# Adafruit_BrainCraft_HAT.net
KiCad netlist of a schematic drawn in EAGLE
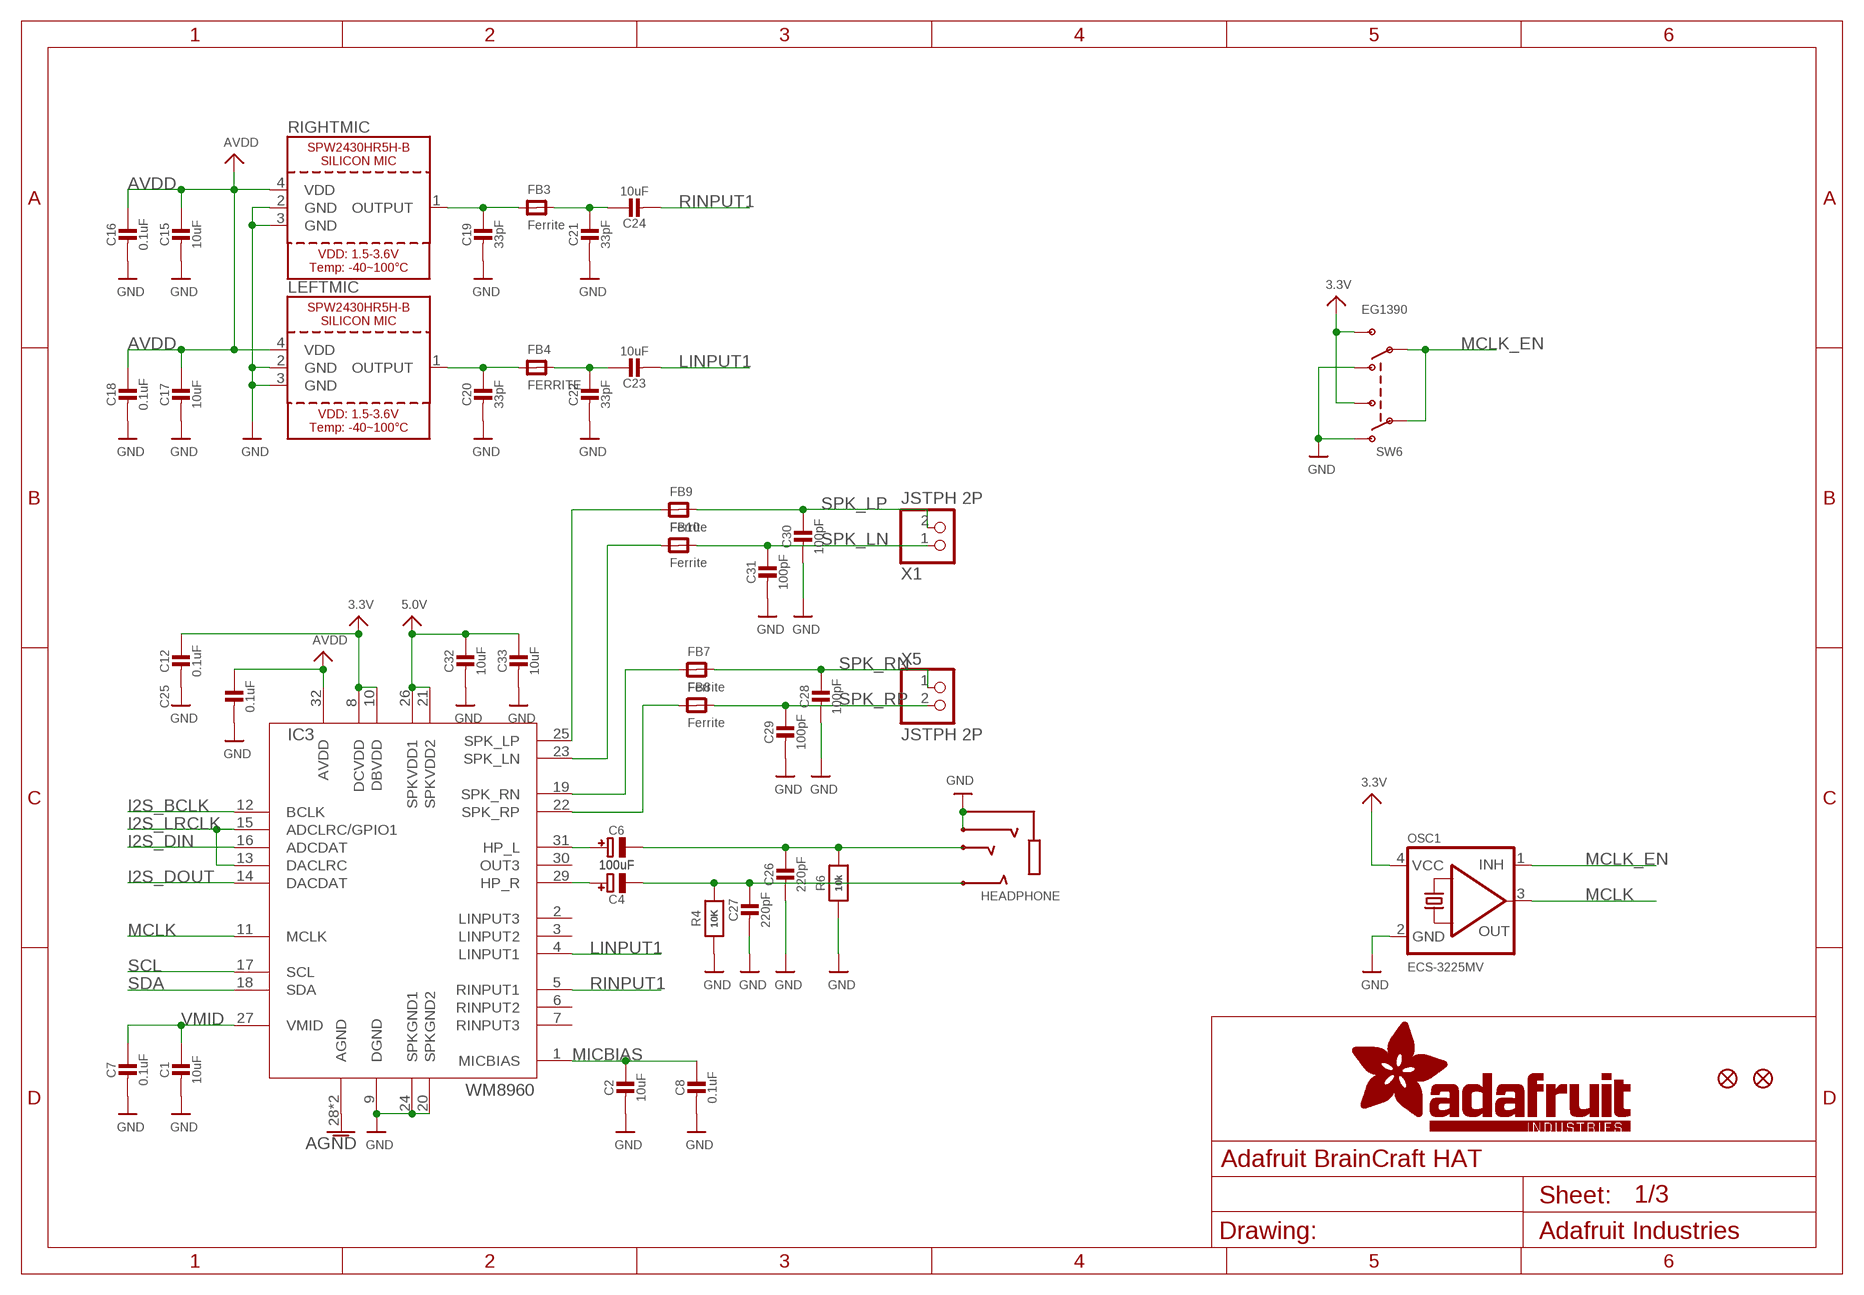
[diagram p0: schematic, sheet 1]
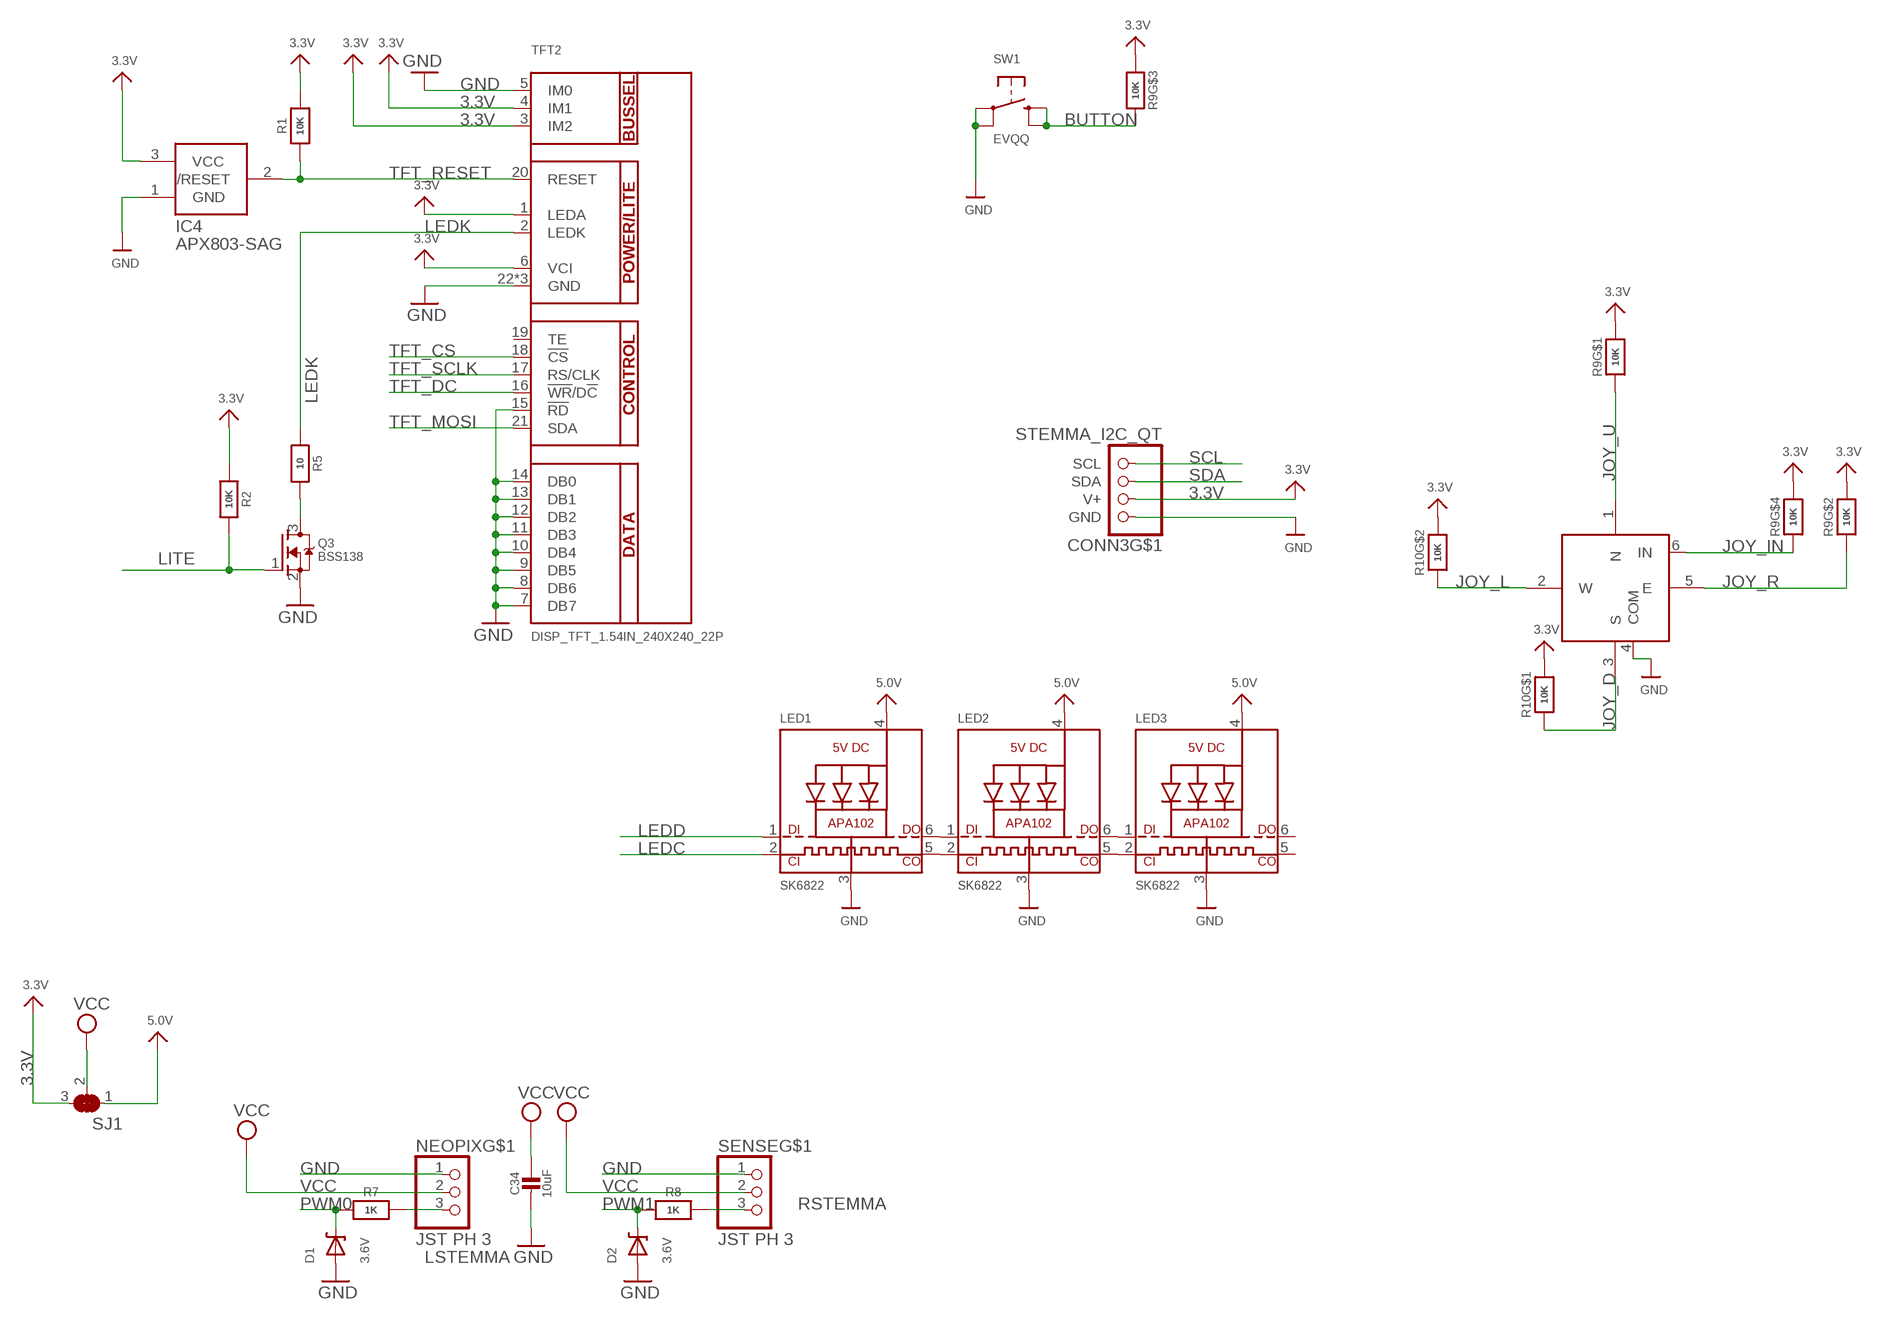
[diagram p1: schematic, sheet 2]
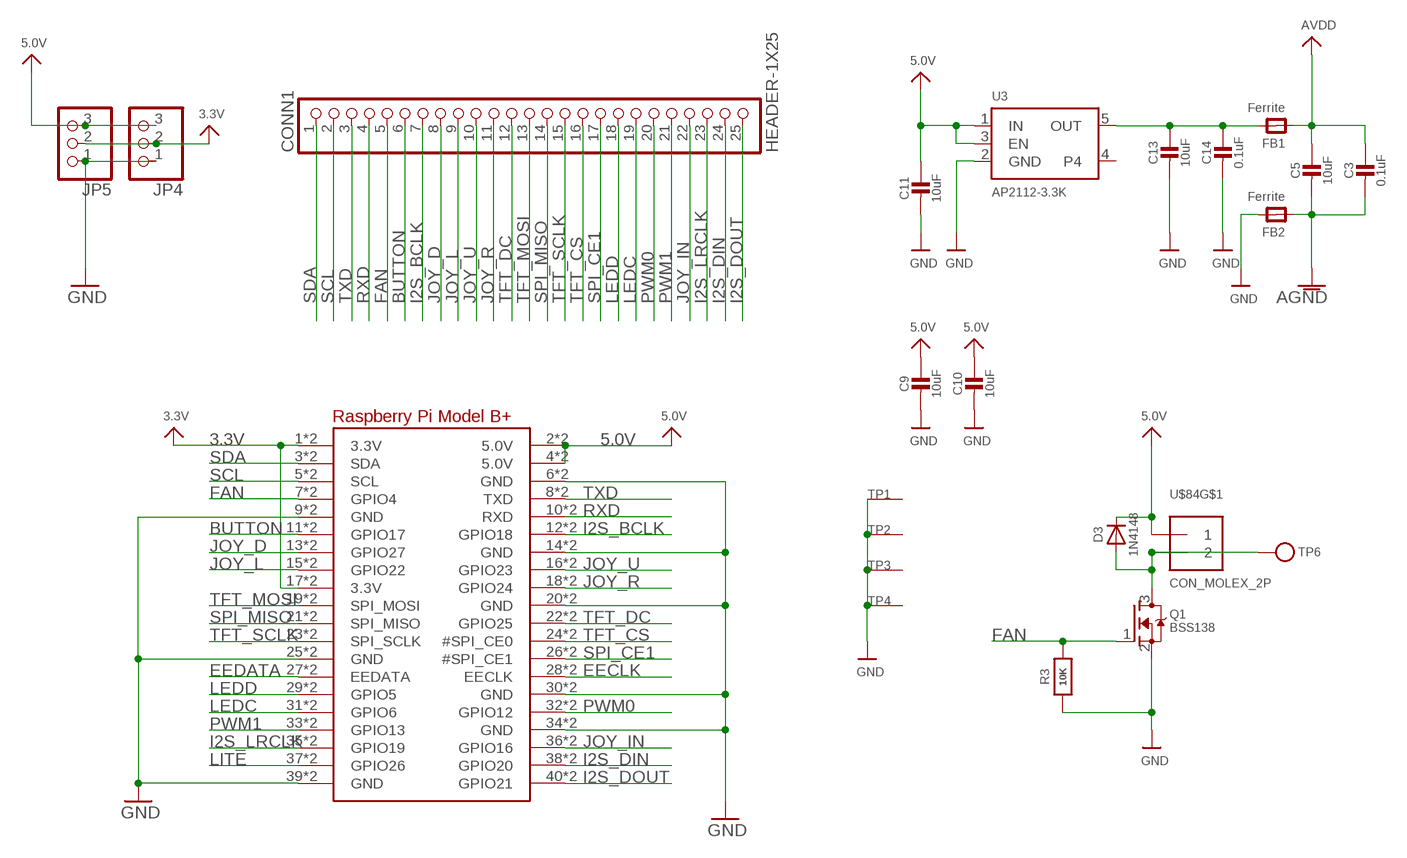
[diagram p2: schematic, sheet 3]

(export (version "E")
  (design (tool "Eeschema 10.0.6"))
  (components
    (comp (ref "C34")
      (value "10uF")
      (footprint "eagle-import:0805-NO")
      (libsource (lib "eagle-import") (part "CAP_CERAMIC0805-NOOUTLINE"))
    )
    (comp (ref "CONN3")
      (value "STEMMA_I2C_QT")
      (footprint "eagle-import:JST_SH4")
      (libsource (lib "eagle-import") (part "STEMMA_I2C_QT"))
    )
    (comp (ref "D1")
      (value "3.6V")
      (footprint "eagle-import:SOD-323")
      (libsource (lib "eagle-import") (part "DIODE-ZENERSOD323"))
    )
    (comp (ref "D2")
      (value "3.6V")
      (footprint "eagle-import:SOD-323")
      (libsource (lib "eagle-import") (part "DIODE-ZENERSOD323"))
    )
    (comp (ref "IC4")
      (value "APX803-SAG")
      (footprint "eagle-import:SOT23")
      (libsource (lib "eagle-import") (part "AXP083-SAG"))
    )
    (comp (ref "LED1")
      (value "SK6822")
      (footprint "eagle-import:APA102")
      (libsource (lib "eagle-import") (part "APA102"))
    )
    (comp (ref "LED2")
      (value "SK6822")
      (footprint "eagle-import:APA102")
      (libsource (lib "eagle-import") (part "APA102"))
    )
    (comp (ref "LED3")
      (value "SK6822")
      (footprint "eagle-import:APA102")
      (libsource (lib "eagle-import") (part "APA102"))
    )
    (comp (ref "NEOPIX")
      (value "JST PH 3")
      (footprint "eagle-import:JSTPH3")
      (libsource (lib "eagle-import") (part "CON_JST_PH_3PIN"))
    )
    (comp (ref "Q3")
      (value "BSS138")
      (footprint "eagle-import:SOT23-WIDE")
      (libsource (lib "eagle-import") (part "MOSFET-NWIDE"))
    )
    (comp (ref "R1")
      (value "10K")
      (footprint "eagle-import:0603-NO")
      (libsource (lib "eagle-import") (part "RESISTOR_0603_NOOUT"))
    )
    (comp (ref "R2")
      (value "10K")
      (footprint "eagle-import:0603-NO")
      (libsource (lib "eagle-import") (part "RESISTOR_0603_NOOUT"))
    )
    (comp (ref "R5")
      (value "10")
      (footprint "eagle-import:0603-NO")
      (libsource (lib "eagle-import") (part "RESISTOR_0603_NOOUT"))
    )
    (comp (ref "R7")
      (value "1K")
      (footprint "eagle-import:0603-NO")
      (libsource (lib "eagle-import") (part "RESISTOR_0603_NOOUT"))
    )
    (comp (ref "R8")
      (value "1K")
      (footprint "eagle-import:0603-NO")
      (libsource (lib "eagle-import") (part "RESISTOR_0603_NOOUT"))
    )
    (comp (ref "R9")
      (value "10K")
      (footprint "eagle-import:RESPACK_4X0603")
      (libsource (lib "eagle-import") (part "RESISTOR_4PACK"))
    )
    (comp (ref "R10")
      (value "10K")
      (footprint "eagle-import:RESPACK_4X0603")
      (libsource (lib "eagle-import") (part "RESISTOR_4PACK"))
    )
    (comp (ref "SENSE")
      (value "JST PH 3")
      (footprint "eagle-import:JSTPH3")
      (libsource (lib "eagle-import") (part "CON_JST_PH_3PIN"))
    )
    (comp (ref "SJ1")
      (value "SOLDERJUMPER_2WAY")
      (footprint "eagle-import:SOLDERJUMPER_2WAY_OPEN_NOPASTE")
      (libsource (lib "eagle-import") (part "SOLDERJUMPER_2WAY"))
    )
    (comp (ref "SW1")
      (value "EVQQ")
      (footprint "eagle-import:EVQ-Q2_SMALLER")
      (libsource (lib "eagle-import") (part "SWITCH_TACT_SMT_EVQQ2_SMALL"))
    )
    (comp (ref "SW5")
      (value "NAVSWITCHSKQUABAUE010")
      (footprint "eagle-import:SKQUBAE010")
      (libsource (lib "eagle-import") (part "NAVSWITCHSKQUABAUE010"))
    )
    (comp (ref "TFT2")
      (value "DISP_TFT_1.54IN_240X240_22P")
      (footprint "eagle-import:TFT_1.54IN_240X240_22PIN")
      (libsource (lib "eagle-import") (part "DISP_TFT_1.54IN_240X240_22P"))
    )
    (comp (ref "C3")
      (value "0.1uF")
      (footprint "eagle-import:0603-NO")
      (libsource (lib "eagle-import") (part "CAP_CERAMIC0603_NO"))
    )
    (comp (ref "C5")
      (value "10uF")
      (footprint "eagle-import:0805-NO")
      (libsource (lib "eagle-import") (part "CAP_CERAMIC0805-NOOUTLINE"))
    )
    (comp (ref "C9")
      (value "10uF")
      (footprint "eagle-import:0805-NO")
      (libsource (lib "eagle-import") (part "CAP_CERAMIC0805-NOOUTLINE"))
    )
    (comp (ref "C10")
      (value "10uF")
      (footprint "eagle-import:0805-NO")
      (libsource (lib "eagle-import") (part "CAP_CERAMIC0805-NOOUTLINE"))
    )
    (comp (ref "C11")
      (value "10uF")
      (footprint "eagle-import:0805-NO")
      (libsource (lib "eagle-import") (part "CAP_CERAMIC0805-NOOUTLINE"))
    )
    (comp (ref "C13")
      (value "10uF")
      (footprint "eagle-import:0805-NO")
      (libsource (lib "eagle-import") (part "CAP_CERAMIC0805-NOOUTLINE"))
    )
    (comp (ref "C14")
      (value "0.1uF")
      (footprint "eagle-import:0603-NO")
      (libsource (lib "eagle-import") (part "CAP_CERAMIC0603_NO"))
    )
    (comp (ref "CONN1")
      (value "HEADER-1X25")
      (footprint "eagle-import:1X25_ROUND_70MIL")
      (libsource (lib "eagle-import") (part "HEADER-1X25"))
    )
    (comp (ref "D3")
      (value "1N4148")
      (footprint "eagle-import:SOD-323")
      (libsource (lib "eagle-import") (part "DIODESOD-323"))
    )
    (comp (ref "FB1")
      (value "Ferrite")
      (footprint "eagle-import:0805")
      (libsource (lib "eagle-import") (part "FERRITE0805"))
    )
    (comp (ref "FB2")
      (value "Ferrite")
      (footprint "eagle-import:0805")
      (libsource (lib "eagle-import") (part "FERRITE0805"))
    )
    (comp (ref "JP4")
      (value "HEADER-1X376MIL")
      (footprint "eagle-import:1X03_ROUND_76")
      (libsource (lib "eagle-import") (part "HEADER-1X376MIL"))
    )
    (comp (ref "JP5")
      (value "HEADER-1X376MIL")
      (footprint "eagle-import:1X03_ROUND_76")
      (libsource (lib "eagle-import") (part "HEADER-1X376MIL"))
    )
    (comp (ref "Q1")
      (value "BSS138")
      (footprint "eagle-import:SOT23-WIDE")
      (libsource (lib "eagle-import") (part "MOSFET-NWIDE"))
    )
    (comp (ref "R3")
      (value "10K")
      (footprint "eagle-import:0603-NO")
      (libsource (lib "eagle-import") (part "RESISTOR_0603_NOOUT"))
    )
    (comp (ref "RPI1")
      (value "RASPBERRYPI_BPLUS_HAT_SMTTHM_SLOTS")
      (footprint "eagle-import:PI_HAT_SMTTHM_SLOTS")
      (libsource (lib "eagle-import") (part "RASPBERRYPI_BPLUS_HAT_SMTTHM_SLOTS"))
    )
    (comp (ref "TP1")
      (value "SEWTAP_SMTNUTM3")
      (footprint "eagle-import:SMT_NUT_3MM")
      (libsource (lib "eagle-import") (part "SEWTAP_SMTNUTM3"))
    )
    (comp (ref "TP2")
      (value "SEWTAP_SMTNUTM3")
      (footprint "eagle-import:SMT_NUT_3MM")
      (libsource (lib "eagle-import") (part "SEWTAP_SMTNUTM3"))
    )
    (comp (ref "TP3")
      (value "SEWTAP_SMTNUTM3")
      (footprint "eagle-import:SMT_NUT_3MM")
      (libsource (lib "eagle-import") (part "SEWTAP_SMTNUTM3"))
    )
    (comp (ref "TP4")
      (value "SEWTAP_SMTNUTM3")
      (footprint "eagle-import:SMT_NUT_3MM")
      (libsource (lib "eagle-import") (part "SEWTAP_SMTNUTM3"))
    )
    (comp (ref "TP6")
      (value "TESTPOINTROUND2MM")
      (footprint "eagle-import:TESTPOINT_ROUND_2MM")
      (libsource (lib "eagle-import") (part "TESTPOINTROUND2MM"))
    )
    (comp (ref "U$84")
      (value "CON_MOLEX_2P")
      (footprint "eagle-import:53398-0271")
      (libsource (lib "eagle-import") (part "CON_MOLEX_2P"))
    )
    (comp (ref "U3")
      (value "AP2112-3.3K")
      (footprint "eagle-import:SOT23-5")
      (libsource (lib "eagle-import") (part "VREG_SOT23-5"))
    )
    (comp (ref "C1")
      (value "10uF")
      (footprint "eagle-import:0805-NO")
      (libsource (lib "eagle-import") (part "CAP_CERAMIC0805-NOOUTLINE"))
    )
    (comp (ref "C2")
      (value "10uF")
      (footprint "eagle-import:0805-NO")
      (libsource (lib "eagle-import") (part "CAP_CERAMIC0805-NOOUTLINE"))
    )
    (comp (ref "C4")
      (value "100uF")
      (footprint "eagle-import:PANASONIC_C")
      (libsource (lib "eagle-import") (part "CAP_ELECTROLYTICPANASONIC_C"))
    )
    (comp (ref "C6")
      (value "100uF")
      (footprint "eagle-import:PANASONIC_C")
      (libsource (lib "eagle-import") (part "CAP_ELECTROLYTICPANASONIC_C"))
    )
    (comp (ref "C7")
      (value "0.1uF")
      (footprint "eagle-import:0603-NO")
      (libsource (lib "eagle-import") (part "CAP_CERAMIC0603_NO"))
    )
    (comp (ref "C8")
      (value "0.1uF")
      (footprint "eagle-import:0603-NO")
      (libsource (lib "eagle-import") (part "CAP_CERAMIC0603_NO"))
    )
    (comp (ref "C12")
      (value "0.1uF")
      (footprint "eagle-import:0603-NO")
      (libsource (lib "eagle-import") (part "CAP_CERAMIC0603_NO"))
    )
    (comp (ref "C15")
      (value "10uF")
      (footprint "eagle-import:0805-NO")
      (libsource (lib "eagle-import") (part "CAP_CERAMIC0805-NOOUTLINE"))
    )
    (comp (ref "C16")
      (value "0.1uF")
      (footprint "eagle-import:0603-NO")
      (libsource (lib "eagle-import") (part "CAP_CERAMIC0603_NO"))
    )
    (comp (ref "C17")
      (value "10uF")
      (footprint "eagle-import:0805-NO")
      (libsource (lib "eagle-import") (part "CAP_CERAMIC0805-NOOUTLINE"))
    )
    (comp (ref "C18")
      (value "0.1uF")
      (footprint "eagle-import:0603-NO")
      (libsource (lib "eagle-import") (part "CAP_CERAMIC0603_NO"))
    )
    (comp (ref "C19")
      (value "33pF")
      (footprint "eagle-import:0603-NO")
      (libsource (lib "eagle-import") (part "CAP_CERAMIC0603_NO"))
    )
    (comp (ref "C20")
      (value "33pF")
      (footprint "eagle-import:0603-NO")
      (libsource (lib "eagle-import") (part "CAP_CERAMIC0603_NO"))
    )
    (comp (ref "C21")
      (value "33pF")
      (footprint "eagle-import:0603-NO")
      (libsource (lib "eagle-import") (part "CAP_CERAMIC0603_NO"))
    )
    (comp (ref "C22")
      (value "33pF")
      (footprint "eagle-import:0603-NO")
      (libsource (lib "eagle-import") (part "CAP_CERAMIC0603_NO"))
    )
    (comp (ref "C23")
      (value "10uF")
      (footprint "eagle-import:0805-NO")
      (libsource (lib "eagle-import") (part "CAP_CERAMIC0805-NOOUTLINE"))
    )
    (comp (ref "C24")
      (value "10uF")
      (footprint "eagle-import:0805-NO")
      (libsource (lib "eagle-import") (part "CAP_CERAMIC0805-NOOUTLINE"))
    )
    (comp (ref "C25")
      (value "0.1uF")
      (footprint "eagle-import:0603-NO")
      (libsource (lib "eagle-import") (part "CAP_CERAMIC0603_NO"))
    )
    (comp (ref "C26")
      (value "220pF")
      (footprint "eagle-import:0603-NO")
      (libsource (lib "eagle-import") (part "CAP_CERAMIC0603_NO"))
    )
    (comp (ref "C27")
      (value "220pF")
      (footprint "eagle-import:0603-NO")
      (libsource (lib "eagle-import") (part "CAP_CERAMIC0603_NO"))
    )
    (comp (ref "C28")
      (value "100pF")
      (footprint "eagle-import:0603-NO")
      (libsource (lib "eagle-import") (part "CAP_CERAMIC0603_NO"))
    )
    (comp (ref "C29")
      (value "100pF")
      (footprint "eagle-import:0603-NO")
      (libsource (lib "eagle-import") (part "CAP_CERAMIC0603_NO"))
    )
    (comp (ref "C30")
      (value "100pF")
      (footprint "eagle-import:0603-NO")
      (libsource (lib "eagle-import") (part "CAP_CERAMIC0603_NO"))
    )
    (comp (ref "C31")
      (value "100pF")
      (footprint "eagle-import:0603-NO")
      (libsource (lib "eagle-import") (part "CAP_CERAMIC0603_NO"))
    )
    (comp (ref "C32")
      (value "10uF")
      (footprint "eagle-import:0805-NO")
      (libsource (lib "eagle-import") (part "CAP_CERAMIC0805-NOOUTLINE"))
    )
    (comp (ref "C33")
      (value "10uF")
      (footprint "eagle-import:0805-NO")
      (libsource (lib "eagle-import") (part "CAP_CERAMIC0805-NOOUTLINE"))
    )
    (comp (ref "FB3")
      (value "Ferrite")
      (footprint "eagle-import:0805-NO")
      (libsource (lib "eagle-import") (part "FERRITE-0805NO"))
    )
    (comp (ref "FB4")
      (value "FERRITE")
      (footprint "eagle-import:0805-NO")
      (libsource (lib "eagle-import") (part "FERRITE-0805NO"))
    )
    (comp (ref "FB7")
      (value "Ferrite")
      (footprint "eagle-import:0805-NO")
      (libsource (lib "eagle-import") (part "FERRITE-0805NO"))
    )
    (comp (ref "FB8")
      (value "Ferrite")
      (footprint "eagle-import:0805-NO")
      (libsource (lib "eagle-import") (part "FERRITE-0805NO"))
    )
    (comp (ref "FB9")
      (value "Ferrite")
      (footprint "eagle-import:0805-NO")
      (libsource (lib "eagle-import") (part "FERRITE-0805NO"))
    )
    (comp (ref "FB10")
      (value "Ferrite")
      (footprint "eagle-import:0805-NO")
      (libsource (lib "eagle-import") (part "FERRITE-0805NO"))
    )
    (comp (ref "FID1")
      (value "FIDUCIAL_1MM")
      (footprint "eagle-import:FIDUCIAL_1MM")
      (libsource (lib "eagle-import") (part "FIDUCIAL_1MM"))
    )
    (comp (ref "FID2")
      (value "FIDUCIAL_1MM")
      (footprint "eagle-import:FIDUCIAL_1MM")
      (libsource (lib "eagle-import") (part "FIDUCIAL_1MM"))
    )
    (comp (ref "HEADPHONE")
      (value "AUDIO_3.5MMJACK_4POL")
      (footprint "eagle-import:4UCONN_18510")
      (libsource (lib "eagle-import") (part "AUDIO_3.5MMJACK_4POL"))
    )
    (comp (ref "IC3")
      (value "WM8960")
      (footprint "eagle-import:QFN32_5MM")
      (libsource (lib "eagle-import") (part "WM8960"))
    )
    (comp (ref "LEFTMIC")
      (value "SPW2430HR5H-B")
      (footprint "eagle-import:SPW2430HR5H-B")
      (libsource (lib "eagle-import") (part "SPW2430HR5H-B"))
    )
    (comp (ref "OSC1")
      (value "ECS-3225MV")
      (footprint "eagle-import:OSC_3.2X2.5MM")
      (libsource (lib "eagle-import") (part "OSCILLATOR3.2X2.5"))
    )
    (comp (ref "R4")
      (value "10K")
      (footprint "eagle-import:0603-NO")
      (libsource (lib "eagle-import") (part "RESISTOR_0603_NOOUT"))
    )
    (comp (ref "R6")
      (value "10k")
      (footprint "eagle-import:0603-NO")
      (libsource (lib "eagle-import") (part "RESISTOR_0603_NOOUT"))
    )
    (comp (ref "RIGHTMIC")
      (value "SPW2430HR5H-B")
      (footprint "eagle-import:SPW2430HR5H-B")
      (libsource (lib "eagle-import") (part "SPW2430HR5H-B"))
    )
    (comp (ref "SW6")
      (value "EG1390")
      (footprint "eagle-import:EG1390")
      (libsource (lib "eagle-import") (part "SWITCH_DPDTEG1390"))
    )
    (comp (ref "X1")
      (value "JSTPH 2P")
      (footprint "eagle-import:JSTPH2")
      (libsource (lib "eagle-import") (part "CON_JST_PH_2PIN"))
    )
    (comp (ref "X5")
      (value "JSTPH 2P")
      (footprint "eagle-import:JSTPH2")
      (libsource (lib "eagle-import") (part "CON_JST_PH_2PIN"))
    )
  )
  (nets
    (net (code "1") (name "3.3V") (class "Default")
      (node (ref "C12") (pin "1") (pinfunction "1_1") (pintype "passive"))
      (node (ref "CONN3") (pin "2") (pinfunction "V+_2") (pintype "passive"))
      (node (ref "IC3") (pin "10") (pinfunction "DBVDD_10") (pintype "power_in"))
      (node (ref "IC3") (pin "8") (pinfunction "DCVDD_8") (pintype "power_in"))
      (node (ref "IC4") (pin "3") (pinfunction "VCC_3") (pintype "power_in"))
      (node (ref "JP4") (pin "2") (pinfunction "2_2") (pintype "passive"))
      (node (ref "JP5") (pin "2") (pinfunction "2_2") (pintype "passive"))
      (node (ref "OSC1") (pin "4") (pinfunction "VCC_4") (pintype "power_in"))
      (node (ref "R1") (pin "2") (pinfunction "2_2") (pintype "passive"))
      (node (ref "R10") (pin "7") (pinfunction "2_7") (pintype "passive"))
      (node (ref "R10") (pin "8") (pinfunction "2_8") (pintype "passive"))
      (node (ref "R2") (pin "2") (pinfunction "2_2") (pintype "passive"))
      (node (ref "R9") (pin "5") (pinfunction "2_5") (pintype "passive"))
      (node (ref "R9") (pin "6") (pinfunction "2_6") (pintype "passive"))
      (node (ref "R9") (pin "7") (pinfunction "2_7") (pintype "passive"))
      (node (ref "R9") (pin "8") (pinfunction "2_8") (pintype "passive"))
      (node (ref "RPI1") (pin "1") (pinfunction "3.3V_1") (pintype "power_in"))
      (node (ref "RPI1") (pin "17") (pinfunction "3.3V_17") (pintype "power_in"))
      (node (ref "RPI1") (pin "S1") (pinfunction "3.3V_S1") (pintype "power_in"))
      (node (ref "RPI1") (pin "S17") (pinfunction "3.3V_S17") (pintype "power_in"))
      (node (ref "SJ1") (pin "3") (pinfunction "3_3") (pintype "passive"))
      (node (ref "SW6") (pin "S1") (pinfunction "S1_S1") (pintype "passive"))
      (node (ref "SW6") (pin "S2") (pinfunction "S2_S2") (pintype "passive"))
      (node (ref "TFT2") (pin "1") (pinfunction "LEDA_1") (pintype "input"))
      (node (ref "TFT2") (pin "3") (pinfunction "IM2_3") (pintype "input"))
      (node (ref "TFT2") (pin "4") (pinfunction "IM1_4") (pintype "input"))
      (node (ref "TFT2") (pin "6") (pinfunction "VCI_6") (pintype "power_in"))
    )
    (net (code "2") (name "5.0V") (class "Default")
      (node (ref "C10") (pin "1") (pinfunction "1_1") (pintype "passive"))
      (node (ref "C11") (pin "1") (pinfunction "1_1") (pintype "passive"))
      (node (ref "C32") (pin "1") (pinfunction "1_1") (pintype "passive"))
      (node (ref "C33") (pin "1") (pinfunction "1_1") (pintype "passive"))
      (node (ref "C9") (pin "1") (pinfunction "1_1") (pintype "passive"))
      (node (ref "D3") (pin "C") (pinfunction "C_C") (pintype "passive"))
      (node (ref "IC3") (pin "21") (pinfunction "SPKVDD2_21") (pintype "power_in"))
      (node (ref "IC3") (pin "26") (pinfunction "SPKVDD1_26") (pintype "power_in"))
      (node (ref "JP4") (pin "3") (pinfunction "3_3") (pintype "passive"))
      (node (ref "JP5") (pin "3") (pinfunction "3_3") (pintype "passive"))
      (node (ref "LED1") (pin "4") (pinfunction "VDD_4") (pintype "power_in"))
      (node (ref "LED2") (pin "4") (pinfunction "VDD_4") (pintype "power_in"))
      (node (ref "LED3") (pin "4") (pinfunction "VDD_4") (pintype "power_in"))
      (node (ref "RPI1") (pin "2") (pinfunction "5.0V_2") (pintype "power_in"))
      (node (ref "RPI1") (pin "4") (pinfunction "5.0V_4") (pintype "power_in"))
      (node (ref "RPI1") (pin "S2") (pinfunction "5.0V_S2") (pintype "power_in"))
      (node (ref "RPI1") (pin "S4") (pinfunction "5.0V_S4") (pintype "power_in"))
      (node (ref "SJ1") (pin "1") (pinfunction "1_1") (pintype "passive"))
      (node (ref "U$84") (pin "1") (pinfunction "1_1") (pintype "passive"))
      (node (ref "U3") (pin "1") (pinfunction "IN_1") (pintype "power_in"))
      (node (ref "U3") (pin "3") (pinfunction "EN_3") (pintype "input"))
    )
    (net (code "3") (name "AGND") (class "Default")
      (node (ref "C3") (pin "2") (pinfunction "2_2") (pintype "passive"))
      (node (ref "C5") (pin "2") (pinfunction "2_2") (pintype "passive"))
      (node (ref "FB2") (pin "1") (pinfunction "P$1_1") (pintype "passive"))
      (node (ref "IC3") (pin "28") (pinfunction "AGND_28") (pintype "power_in"))
      (node (ref "IC3") (pin "33") (pinfunction "AGND_33") (pintype "power_in"))
    )
    (net (code "4") (name "AVDD") (class "Default")
      (node (ref "C15") (pin "1") (pinfunction "1_1") (pintype "passive"))
      (node (ref "C16") (pin "1") (pinfunction "1_1") (pintype "passive"))
      (node (ref "C17") (pin "1") (pinfunction "1_1") (pintype "passive"))
      (node (ref "C18") (pin "1") (pinfunction "1_1") (pintype "passive"))
      (node (ref "C25") (pin "1") (pinfunction "1_1") (pintype "passive"))
      (node (ref "C3") (pin "1") (pinfunction "1_1") (pintype "passive"))
      (node (ref "C5") (pin "1") (pinfunction "1_1") (pintype "passive"))
      (node (ref "FB1") (pin "1") (pinfunction "P$1_1") (pintype "passive"))
      (node (ref "IC3") (pin "32") (pinfunction "AVDD_32") (pintype "power_in"))
      (node (ref "LEFTMIC") (pin "4") (pinfunction "VDD_4") (pintype "power_in"))
      (node (ref "RIGHTMIC") (pin "4") (pinfunction "VDD_4") (pintype "power_in"))
    )
    (net (code "5") (name "BUTTON") (class "Default")
      (node (ref "CONN1") (pin "6") (pinfunction "6_6") (pintype "passive"))
      (node (ref "R9") (pin "3") (pinfunction "1_3") (pintype "passive"))
      (node (ref "RPI1") (pin "11") (pinfunction "GPIO17_11") (pintype "bidirectional"))
      (node (ref "RPI1") (pin "S11") (pinfunction "GPIO17_S11") (pintype "bidirectional"))
      (node (ref "SW1") (pin "B") (pinfunction "S_B") (pintype "passive"))
      (node (ref "SW1") (pin "B'") (pinfunction "S1_B'") (pintype "passive"))
    )
    (net (code "6") (name "EECLK") (class "Default")
      (node (ref "RPI1") (pin "28") (pinfunction "EECLK_28") (pintype "bidirectional"))
      (node (ref "RPI1") (pin "S28") (pinfunction "EECLK_S28") (pintype "bidirectional"))
    )
    (net (code "7") (name "EEDATA") (class "Default")
      (node (ref "RPI1") (pin "27") (pinfunction "EEDATA_27") (pintype "bidirectional"))
      (node (ref "RPI1") (pin "S27") (pinfunction "EEDATA_S27") (pintype "bidirectional"))
    )
    (net (code "8") (name "FAN") (class "Default")
      (node (ref "CONN1") (pin "5") (pinfunction "5_5") (pintype "passive"))
      (node (ref "Q1") (pin "1") (pinfunction "G_1") (pintype "bidirectional"))
      (node (ref "R3") (pin "1") (pinfunction "1_1") (pintype "passive"))
      (node (ref "RPI1") (pin "7") (pinfunction "GPIO4_7") (pintype "bidirectional"))
      (node (ref "RPI1") (pin "S7") (pinfunction "GPIO4_S7") (pintype "bidirectional"))
    )
    (net (code "9") (name "GND") (class "Default")
      (node (ref "C1") (pin "2") (pinfunction "2_2") (pintype "passive"))
      (node (ref "C10") (pin "2") (pinfunction "2_2") (pintype "passive"))
      (node (ref "C11") (pin "2") (pinfunction "2_2") (pintype "passive"))
      (node (ref "C12") (pin "2") (pinfunction "2_2") (pintype "passive"))
      (node (ref "C13") (pin "2") (pinfunction "2_2") (pintype "passive"))
      (node (ref "C14") (pin "2") (pinfunction "2_2") (pintype "passive"))
      (node (ref "C15") (pin "2") (pinfunction "2_2") (pintype "passive"))
      (node (ref "C16") (pin "2") (pinfunction "2_2") (pintype "passive"))
      (node (ref "C17") (pin "2") (pinfunction "2_2") (pintype "passive"))
      (node (ref "C18") (pin "2") (pinfunction "2_2") (pintype "passive"))
      (node (ref "C19") (pin "2") (pinfunction "2_2") (pintype "passive"))
      (node (ref "C2") (pin "2") (pinfunction "2_2") (pintype "passive"))
      (node (ref "C20") (pin "2") (pinfunction "2_2") (pintype "passive"))
      (node (ref "C21") (pin "2") (pinfunction "2_2") (pintype "passive"))
      (node (ref "C22") (pin "2") (pinfunction "2_2") (pintype "passive"))
      (node (ref "C25") (pin "2") (pinfunction "2_2") (pintype "passive"))
      (node (ref "C26") (pin "2") (pinfunction "2_2") (pintype "passive"))
      (node (ref "C27") (pin "2") (pinfunction "2_2") (pintype "passive"))
      (node (ref "C28") (pin "2") (pinfunction "2_2") (pintype "passive"))
      (node (ref "C29") (pin "2") (pinfunction "2_2") (pintype "passive"))
      (node (ref "C30") (pin "2") (pinfunction "2_2") (pintype "passive"))
      (node (ref "C31") (pin "2") (pinfunction "2_2") (pintype "passive"))
      (node (ref "C32") (pin "2") (pinfunction "2_2") (pintype "passive"))
      (node (ref "C33") (pin "2") (pinfunction "2_2") (pintype "passive"))
      (node (ref "C34") (pin "2") (pinfunction "2_2") (pintype "passive"))
      (node (ref "C7") (pin "2") (pinfunction "2_2") (pintype "passive"))
      (node (ref "C8") (pin "2") (pinfunction "2_2") (pintype "passive"))
      (node (ref "C9") (pin "2") (pinfunction "2_2") (pintype "passive"))
      (node (ref "CONN3") (pin "1") (pinfunction "GND_1") (pintype "passive"))
      (node (ref "D1") (pin "A") (pinfunction "A_A") (pintype "passive"))
      (node (ref "D2") (pin "A") (pinfunction "A_A") (pintype "passive"))
      (node (ref "FB2") (pin "2") (pinfunction "P$2_2") (pintype "passive"))
      (node (ref "HEADPHONE") (pin "1-GND") (pinfunction "TIP_1-GND") (pintype "passive"))
      (node (ref "HEADPHONE") (pin "4-INNER_SLEEVE") (pinfunction "RING1_4-INNER_SLEEVE") (pintype "passive"))
      (node (ref "IC3") (pin "20") (pinfunction "SPKGND2_20") (pintype "power_in"))
      (node (ref "IC3") (pin "24") (pinfunction "SPKGND1_24") (pintype "power_in"))
      (node (ref "IC3") (pin "9") (pinfunction "DGND_9") (pintype "power_in"))
      (node (ref "IC4") (pin "1") (pinfunction "GND_1") (pintype "power_in"))
      (node (ref "JP4") (pin "1") (pinfunction "1_1") (pintype "passive"))
      (node (ref "JP5") (pin "1") (pinfunction "1_1") (pintype "passive"))
      (node (ref "LED1") (pin "3") (pinfunction "GND_3") (pintype "power_in"))
      (node (ref "LED2") (pin "3") (pinfunction "GND_3") (pintype "power_in"))
      (node (ref "LED3") (pin "3") (pinfunction "GND_3") (pintype "power_in"))
      (node (ref "LEFTMIC") (pin "2") (pinfunction "GND_2") (pintype "power_in"))
      (node (ref "LEFTMIC") (pin "3") (pinfunction "GND_3") (pintype "power_in"))
      (node (ref "NEOPIX") (pin "1") (pinfunction "1_1") (pintype "passive"))
      (node (ref "OSC1") (pin "2") (pinfunction "GND_2") (pintype "power_in"))
      (node (ref "Q1") (pin "2") (pinfunction "S_2") (pintype "bidirectional"))
      (node (ref "Q3") (pin "2") (pinfunction "S_2") (pintype "bidirectional"))
      (node (ref "R3") (pin "2") (pinfunction "2_2") (pintype "passive"))
      (node (ref "R4") (pin "1") (pinfunction "1_1") (pintype "passive"))
      (node (ref "R6") (pin "1") (pinfunction "1_1") (pintype "passive"))
      (node (ref "RIGHTMIC") (pin "2") (pinfunction "GND_2") (pintype "power_in"))
      (node (ref "RIGHTMIC") (pin "3") (pinfunction "GND_3") (pintype "power_in"))
      (node (ref "RPI1") (pin "14") (pinfunction "GND_14") (pintype "power_in"))
      (node (ref "RPI1") (pin "20") (pinfunction "GND_20") (pintype "power_in"))
      (node (ref "RPI1") (pin "25") (pinfunction "GND_25") (pintype "power_in"))
      (node (ref "RPI1") (pin "30") (pinfunction "GND_30") (pintype "power_in"))
      (node (ref "RPI1") (pin "34") (pinfunction "GND_34") (pintype "power_in"))
      (node (ref "RPI1") (pin "39") (pinfunction "GND_39") (pintype "power_in"))
      (node (ref "RPI1") (pin "6") (pinfunction "GND_6") (pintype "power_in"))
      (node (ref "RPI1") (pin "9") (pinfunction "GND_9") (pintype "power_in"))
      (node (ref "RPI1") (pin "S14") (pinfunction "GND_S14") (pintype "power_in"))
      (node (ref "RPI1") (pin "S20") (pinfunction "GND_S20") (pintype "power_in"))
      (node (ref "RPI1") (pin "S25") (pinfunction "GND_S25") (pintype "power_in"))
      (node (ref "RPI1") (pin "S30") (pinfunction "GND_S30") (pintype "power_in"))
      (node (ref "RPI1") (pin "S34") (pinfunction "GND_S34") (pintype "power_in"))
      (node (ref "RPI1") (pin "S39") (pinfunction "GND_S39") (pintype "power_in"))
      (node (ref "RPI1") (pin "S6") (pinfunction "GND_S6") (pintype "power_in"))
      (node (ref "RPI1") (pin "S9") (pinfunction "GND_S9") (pintype "power_in"))
      (node (ref "SENSE") (pin "1") (pinfunction "1_1") (pintype "passive"))
      (node (ref "SW1") (pin "A") (pinfunction "P_A") (pintype "passive"))
      (node (ref "SW1") (pin "A'") (pinfunction "P1_A'") (pintype "passive"))
      (node (ref "SW5") (pin "4") (pinfunction "COM_4") (pintype "bidirectional"))
      (node (ref "SW6") (pin "O1") (pinfunction "O1_O1") (pintype "passive"))
      (node (ref "SW6") (pin "O2") (pinfunction "O2_O2") (pintype "passive"))
      (node (ref "TFT2") (pin "10") (pinfunction "DB4_10") (pintype "bidirectional"))
      (node (ref "TFT2") (pin "11") (pinfunction "DB3_11") (pintype "bidirectional"))
      (node (ref "TFT2") (pin "12") (pinfunction "DB2_12") (pintype "bidirectional"))
      (node (ref "TFT2") (pin "13") (pinfunction "DB1_13") (pintype "bidirectional"))
      (node (ref "TFT2") (pin "14") (pinfunction "DB0_14") (pintype "bidirectional"))
      (node (ref "TFT2") (pin "15") (pinfunction "~{RD}_15") (pintype "input"))
      (node (ref "TFT2") (pin "22") (pinfunction "GND_22") (pintype "power_in"))
      (node (ref "TFT2") (pin "5") (pinfunction "IM0_5") (pintype "input"))
      (node (ref "TFT2") (pin "7") (pinfunction "DB7_7") (pintype "bidirectional"))
      (node (ref "TFT2") (pin "8") (pinfunction "DB6_8") (pintype "bidirectional"))
      (node (ref "TFT2") (pin "9") (pinfunction "DB5_9") (pintype "bidirectional"))
      (node (ref "TFT2") (pin "SUPPORT1") (pinfunction "GND_SUPPORT1") (pintype "power_in"))
      (node (ref "TFT2") (pin "SUPPORT2") (pinfunction "GND_SUPPORT2") (pintype "power_in"))
      (node (ref "TP1") (pin "P$1") (pinfunction "SEW_P$1") (pintype "bidirectional"))
      (node (ref "TP2") (pin "P$1") (pinfunction "SEW_P$1") (pintype "bidirectional"))
      (node (ref "TP3") (pin "P$1") (pinfunction "SEW_P$1") (pintype "bidirectional"))
      (node (ref "TP4") (pin "P$1") (pinfunction "SEW_P$1") (pintype "bidirectional"))
      (node (ref "U3") (pin "2") (pinfunction "GND_2") (pintype "power_in"))
    )
    (net (code "10") (name "I2S_BCLK") (class "Default")
      (node (ref "CONN1") (pin "7") (pinfunction "7_7") (pintype "passive"))
      (node (ref "IC3") (pin "12") (pinfunction "BCLK_12") (pintype "bidirectional"))
      (node (ref "RPI1") (pin "12") (pinfunction "GPIO18_12") (pintype "bidirectional"))
      (node (ref "RPI1") (pin "S12") (pinfunction "GPIO18_S12") (pintype "bidirectional"))
    )
    (net (code "11") (name "I2S_DIN") (class "Default")
      (node (ref "CONN1") (pin "24") (pinfunction "24_24") (pintype "passive"))
      (node (ref "IC3") (pin "16") (pinfunction "ADCDAT_16") (pintype "input"))
      (node (ref "RPI1") (pin "38") (pinfunction "GPIO20_38") (pintype "bidirectional"))
      (node (ref "RPI1") (pin "S38") (pinfunction "GPIO20_S38") (pintype "bidirectional"))
    )
    (net (code "12") (name "I2S_DOUT") (class "Default")
      (node (ref "CONN1") (pin "25") (pinfunction "25_25") (pintype "passive"))
      (node (ref "IC3") (pin "14") (pinfunction "DACDAT_14") (pintype "bidirectional"))
      (node (ref "RPI1") (pin "40") (pinfunction "GPIO21_40") (pintype "bidirectional"))
      (node (ref "RPI1") (pin "S40") (pinfunction "GPIO21_S40") (pintype "bidirectional"))
    )
    (net (code "13") (name "I2S_LRCLK") (class "Default")
      (node (ref "CONN1") (pin "23") (pinfunction "23_23") (pintype "passive"))
      (node (ref "IC3") (pin "13") (pinfunction "DACLRC_13") (pintype "bidirectional"))
      (node (ref "IC3") (pin "15") (pinfunction "ADCLRC/GPIO1_15") (pintype "bidirectional"))
      (node (ref "RPI1") (pin "35") (pinfunction "GPIO19_35") (pintype "bidirectional"))
      (node (ref "RPI1") (pin "S35") (pinfunction "GPIO19_S35") (pintype "bidirectional"))
    )
    (net (code "14") (name "JOY_D") (class "Default")
      (node (ref "CONN1") (pin "8") (pinfunction "8_8") (pintype "passive"))
      (node (ref "R10") (pin "1") (pinfunction "1_1") (pintype "passive"))
      (node (ref "RPI1") (pin "13") (pinfunction "GPIO27_13") (pintype "bidirectional"))
      (node (ref "RPI1") (pin "S13") (pinfunction "GPIO27_S13") (pintype "bidirectional"))
      (node (ref "SW5") (pin "3") (pinfunction "S_3") (pintype "bidirectional"))
    )
    (net (code "15") (name "JOY_IN") (class "Default")
      (node (ref "CONN1") (pin "22") (pinfunction "22_22") (pintype "passive"))
      (node (ref "R9") (pin "4") (pinfunction "1_4") (pintype "passive"))
      (node (ref "RPI1") (pin "36") (pinfunction "GPIO16_36") (pintype "bidirectional"))
      (node (ref "RPI1") (pin "S36") (pinfunction "GPIO16_S36") (pintype "bidirectional"))
      (node (ref "SW5") (pin "6") (pinfunction "IN_6") (pintype "bidirectional"))
    )
    (net (code "16") (name "JOY_L") (class "Default")
      (node (ref "CONN1") (pin "9") (pinfunction "9_9") (pintype "passive"))
      (node (ref "R10") (pin "2") (pinfunction "1_2") (pintype "passive"))
      (node (ref "RPI1") (pin "15") (pinfunction "GPIO22_15") (pintype "bidirectional"))
      (node (ref "RPI1") (pin "S15") (pinfunction "GPIO22_S15") (pintype "bidirectional"))
      (node (ref "SW5") (pin "2") (pinfunction "W_2") (pintype "bidirectional"))
    )
    (net (code "17") (name "JOY_R") (class "Default")
      (node (ref "CONN1") (pin "11") (pinfunction "11_11") (pintype "passive"))
      (node (ref "R9") (pin "2") (pinfunction "1_2") (pintype "passive"))
      (node (ref "RPI1") (pin "18") (pinfunction "GPIO24_18") (pintype "bidirectional"))
      (node (ref "RPI1") (pin "S18") (pinfunction "GPIO24_S18") (pintype "bidirectional"))
      (node (ref "SW5") (pin "5") (pinfunction "E_5") (pintype "bidirectional"))
    )
    (net (code "18") (name "JOY_U") (class "Default")
      (node (ref "CONN1") (pin "10") (pinfunction "10_10") (pintype "passive"))
      (node (ref "R9") (pin "1") (pinfunction "1_1") (pintype "passive"))
      (node (ref "RPI1") (pin "16") (pinfunction "GPIO23_16") (pintype "bidirectional"))
      (node (ref "RPI1") (pin "S16") (pinfunction "GPIO23_S16") (pintype "bidirectional"))
      (node (ref "SW5") (pin "1") (pinfunction "N_1") (pintype "bidirectional"))
    )
    (net (code "19") (name "LEDC") (class "Default")
      (node (ref "CONN1") (pin "19") (pinfunction "19_19") (pintype "passive"))
      (node (ref "LED1") (pin "2") (pinfunction "CKI_2") (pintype "input"))
      (node (ref "RPI1") (pin "31") (pinfunction "GPIO6_31") (pintype "bidirectional"))
      (node (ref "RPI1") (pin "S31") (pinfunction "GPIO6_S31") (pintype "bidirectional"))
    )
    (net (code "20") (name "LEDD") (class "Default")
      (node (ref "CONN1") (pin "18") (pinfunction "18_18") (pintype "passive"))
      (node (ref "LED1") (pin "1") (pinfunction "DI_1") (pintype "input"))
      (node (ref "RPI1") (pin "29") (pinfunction "GPIO5_29") (pintype "bidirectional"))
      (node (ref "RPI1") (pin "S29") (pinfunction "GPIO5_S29") (pintype "bidirectional"))
    )
    (net (code "21") (name "LEDK") (class "Default")
      (node (ref "R5") (pin "2") (pinfunction "2_2") (pintype "passive"))
      (node (ref "TFT2") (pin "2") (pinfunction "LEDK_2") (pintype "input"))
    )
    (net (code "22") (name "LINPUT1") (class "Default")
      (node (ref "C23") (pin "2") (pinfunction "2_2") (pintype "passive"))
      (node (ref "IC3") (pin "4") (pinfunction "LINPUT1_4") (pintype "input"))
    )
    (net (code "23") (name "LITE") (class "Default")
      (node (ref "Q3") (pin "1") (pinfunction "G_1") (pintype "bidirectional"))
      (node (ref "R2") (pin "1") (pinfunction "1_1") (pintype "passive"))
      (node (ref "RPI1") (pin "37") (pinfunction "GPIO26_37") (pintype "bidirectional"))
      (node (ref "RPI1") (pin "S37") (pinfunction "GPIO26_S37") (pintype "bidirectional"))
    )
    (net (code "24") (name "LSTEMMA") (class "Default")
      (node (ref "NEOPIX") (pin "3") (pinfunction "3_3") (pintype "passive"))
      (node (ref "R7") (pin "1") (pinfunction "1_1") (pintype "passive"))
    )
    (net (code "25") (name "MCLK") (class "Default")
      (node (ref "IC3") (pin "11") (pinfunction "MCLK_11") (pintype "input"))
      (node (ref "OSC1") (pin "3") (pinfunction "OUT_3") (pintype "output"))
    )
    (net (code "26") (name "MCLK_EN") (class "Default")
      (node (ref "OSC1") (pin "1") (pinfunction "INH_1") (pintype "bidirectional"))
      (node (ref "SW6") (pin "P1") (pinfunction "P1_P1") (pintype "passive"))
      (node (ref "SW6") (pin "P2") (pinfunction "P2_P2") (pintype "passive"))
    )
    (net (code "27") (name "MICBIAS") (class "Default")
      (node (ref "C2") (pin "1") (pinfunction "1_1") (pintype "passive"))
      (node (ref "C8") (pin "1") (pinfunction "1_1") (pintype "passive"))
      (node (ref "IC3") (pin "1") (pinfunction "MICBIAS_1") (pintype "output"))
    )
    (net (code "28") (name "Net-(FB1-P$2)") (class "Default")
      (node (ref "C13") (pin "1") (pinfunction "1_1") (pintype "passive"))
      (node (ref "C14") (pin "1") (pinfunction "1_1") (pintype "passive"))
      (node (ref "FB1") (pin "2") (pinfunction "P$2_2") (pintype "passive"))
      (node (ref "U3") (pin "5") (pinfunction "OUT_5") (pintype "power_in"))
    )
    (net (code "29") (name "Net-(FB3-P$1)") (class "Default")
      (node (ref "C19") (pin "1") (pinfunction "1_1") (pintype "passive"))
      (node (ref "FB3") (pin "1") (pinfunction "P$1_1") (pintype "passive"))
      (node (ref "RIGHTMIC") (pin "1") (pinfunction "OUTPUT_1") (pintype "output"))
    )
    (net (code "30") (name "Net-(FB3-P$2)") (class "Default")
      (node (ref "C21") (pin "1") (pinfunction "1_1") (pintype "passive"))
      (node (ref "C24") (pin "1") (pinfunction "1_1") (pintype "passive"))
      (node (ref "FB3") (pin "2") (pinfunction "P$2_2") (pintype "passive"))
    )
    (net (code "31") (name "Net-(FB4-P$1)") (class "Default")
      (node (ref "C20") (pin "1") (pinfunction "1_1") (pintype "passive"))
      (node (ref "FB4") (pin "1") (pinfunction "P$1_1") (pintype "passive"))
      (node (ref "LEFTMIC") (pin "1") (pinfunction "OUTPUT_1") (pintype "output"))
    )
    (net (code "32") (name "Net-(FB4-P$2)") (class "Default")
      (node (ref "C22") (pin "1") (pinfunction "1_1") (pintype "passive"))
      (node (ref "C23") (pin "1") (pinfunction "1_1") (pintype "passive"))
      (node (ref "FB4") (pin "2") (pinfunction "P$2_2") (pintype "passive"))
    )
    (net (code "33") (name "Net-(FB7-P$1)") (class "Default")
      (node (ref "FB7") (pin "1") (pinfunction "P$1_1") (pintype "passive"))
      (node (ref "IC3") (pin "19") (pinfunction "SPK_RN_19") (pintype "output"))
    )
    (net (code "34") (name "Net-(FB8-P$1)") (class "Default")
      (node (ref "FB8") (pin "1") (pinfunction "P$1_1") (pintype "passive"))
      (node (ref "IC3") (pin "22") (pinfunction "SPK_RP_22") (pintype "output"))
    )
    (net (code "35") (name "Net-(FB9-P$1)") (class "Default")
      (node (ref "FB9") (pin "1") (pinfunction "P$1_1") (pintype "passive"))
      (node (ref "IC3") (pin "25") (pinfunction "SPK_LP_25") (pintype "output"))
    )
    (net (code "36") (name "Net-(FB10-P$1)") (class "Default")
      (node (ref "FB10") (pin "1") (pinfunction "P$1_1") (pintype "passive"))
      (node (ref "IC3") (pin "23") (pinfunction "SPK_LN_23") (pintype "output"))
    )
    (net (code "37") (name "Net-(HEADPHONE-RING2)") (class "Default")
      (node (ref "C27") (pin "1") (pinfunction "1_1") (pintype "passive"))
      (node (ref "C4") (pin "-") (pinfunction "-_-") (pintype "passive"))
      (node (ref "HEADPHONE") (pin "3-OUTER_SLEEVE") (pinfunction "RING2_3-OUTER_SLEEVE") (pintype "passive"))
      (node (ref "R4") (pin "2") (pinfunction "2_2") (pintype "passive"))
    )
    (net (code "38") (name "Net-(HEADPHONE-RING3)") (class "Default")
      (node (ref "C26") (pin "1") (pinfunction "1_1") (pintype "passive"))
      (node (ref "C6") (pin "-") (pinfunction "-_-") (pintype "passive"))
      (node (ref "HEADPHONE") (pin "2-TIP") (pinfunction "RING3_2-TIP") (pintype "passive"))
      (node (ref "R6") (pin "2") (pinfunction "2_2") (pintype "passive"))
    )
    (net (code "39") (name "Net-(IC3-HP_L)") (class "Default")
      (node (ref "C6") (pin "+") (pinfunction "+_+") (pintype "passive"))
      (node (ref "IC3") (pin "31") (pinfunction "HP_L_31") (pintype "output"))
    )
    (net (code "40") (name "Net-(IC3-HP_R)") (class "Default")
      (node (ref "C4") (pin "+") (pinfunction "+_+") (pintype "passive"))
      (node (ref "IC3") (pin "29") (pinfunction "HP_R_29") (pintype "output"))
    )
    (net (code "41") (name "Net-(LED1-CKO)") (class "Default")
      (node (ref "LED1") (pin "5") (pinfunction "CKO_5") (pintype "output"))
      (node (ref "LED2") (pin "2") (pinfunction "CKI_2") (pintype "input"))
    )
    (net (code "42") (name "Net-(LED1-DO)") (class "Default")
      (node (ref "LED1") (pin "6") (pinfunction "DO_6") (pintype "output"))
      (node (ref "LED2") (pin "1") (pinfunction "DI_1") (pintype "input"))
    )
    (net (code "43") (name "Net-(LED2-CKO)") (class "Default")
      (node (ref "LED2") (pin "5") (pinfunction "CKO_5") (pintype "output"))
      (node (ref "LED3") (pin "2") (pinfunction "CKI_2") (pintype "input"))
    )
    (net (code "44") (name "Net-(LED2-DO)") (class "Default")
      (node (ref "LED2") (pin "6") (pinfunction "DO_6") (pintype "output"))
      (node (ref "LED3") (pin "1") (pinfunction "DI_1") (pintype "input"))
    )
    (net (code "45") (name "Net-(Q1-D)") (class "Default")
      (node (ref "D3") (pin "A") (pinfunction "A_A") (pintype "passive"))
      (node (ref "Q1") (pin "3") (pinfunction "D_3") (pintype "bidirectional"))
      (node (ref "TP6") (pin "P$1") (pinfunction "P$1_P$1") (pintype "bidirectional"))
      (node (ref "U$84") (pin "2") (pinfunction "2_2") (pintype "passive"))
    )
    (net (code "46") (name "Net-(Q3-D)") (class "Default")
      (node (ref "Q3") (pin "3") (pinfunction "D_3") (pintype "bidirectional"))
      (node (ref "R5") (pin "1") (pinfunction "1_1") (pintype "passive"))
    )
    (net (code "47") (name "PWM0") (class "Default")
      (node (ref "CONN1") (pin "20") (pinfunction "20_20") (pintype "passive"))
      (node (ref "D1") (pin "C") (pinfunction "C_C") (pintype "passive"))
      (node (ref "R7") (pin "2") (pinfunction "2_2") (pintype "passive"))
      (node (ref "RPI1") (pin "32") (pinfunction "GPIO12_32") (pintype "bidirectional"))
      (node (ref "RPI1") (pin "S32") (pinfunction "GPIO12_S32") (pintype "bidirectional"))
    )
    (net (code "48") (name "PWM1") (class "Default")
      (node (ref "CONN1") (pin "21") (pinfunction "21_21") (pintype "passive"))
      (node (ref "D2") (pin "C") (pinfunction "C_C") (pintype "passive"))
      (node (ref "R8") (pin "2") (pinfunction "2_2") (pintype "passive"))
      (node (ref "RPI1") (pin "33") (pinfunction "GPIO13_33") (pintype "bidirectional"))
      (node (ref "RPI1") (pin "S33") (pinfunction "GPIO13_S33") (pintype "bidirectional"))
    )
    (net (code "49") (name "RINPUT1") (class "Default")
      (node (ref "C24") (pin "2") (pinfunction "2_2") (pintype "passive"))
      (node (ref "IC3") (pin "5") (pinfunction "RINPUT1_5") (pintype "input"))
    )
    (net (code "50") (name "RSTEMMA") (class "Default")
      (node (ref "R8") (pin "1") (pinfunction "1_1") (pintype "passive"))
      (node (ref "SENSE") (pin "3") (pinfunction "3_3") (pintype "passive"))
    )
    (net (code "51") (name "RXD") (class "Default")
      (node (ref "CONN1") (pin "4") (pinfunction "4_4") (pintype "passive"))
      (node (ref "RPI1") (pin "10") (pinfunction "RXD_10") (pintype "bidirectional"))
      (node (ref "RPI1") (pin "S10") (pinfunction "RXD_S10") (pintype "bidirectional"))
    )
    (net (code "52") (name "SCL") (class "Default")
      (node (ref "CONN1") (pin "2") (pinfunction "2_2") (pintype "passive"))
      (node (ref "CONN3") (pin "4") (pinfunction "SCL_4") (pintype "passive"))
      (node (ref "IC3") (pin "17") (pinfunction "SCL_17") (pintype "input"))
      (node (ref "RPI1") (pin "5") (pinfunction "SCL_5") (pintype "bidirectional"))
      (node (ref "RPI1") (pin "S5") (pinfunction "SCL_S5") (pintype "bidirectional"))
    )
    (net (code "53") (name "SDA") (class "Default")
      (node (ref "CONN1") (pin "1") (pinfunction "1_1") (pintype "passive"))
      (node (ref "CONN3") (pin "3") (pinfunction "SDA_3") (pintype "passive"))
      (node (ref "IC3") (pin "18") (pinfunction "SDA_18") (pintype "bidirectional"))
      (node (ref "RPI1") (pin "3") (pinfunction "SDA_3") (pintype "bidirectional"))
      (node (ref "RPI1") (pin "S3") (pinfunction "SDA_S3") (pintype "bidirectional"))
    )
    (net (code "54") (name "SPI_CE1") (class "Default")
      (node (ref "CONN1") (pin "17") (pinfunction "17_17") (pintype "passive"))
      (node (ref "RPI1") (pin "26") (pinfunction "#SPI_CE1_26") (pintype "bidirectional"))
      (node (ref "RPI1") (pin "S26") (pinfunction "#SPI_CE1_S26") (pintype "bidirectional"))
    )
    (net (code "55") (name "SPI_MISO") (class "Default")
      (node (ref "CONN1") (pin "14") (pinfunction "14_14") (pintype "passive"))
      (node (ref "RPI1") (pin "21") (pinfunction "SPI_MISO_21") (pintype "bidirectional"))
      (node (ref "RPI1") (pin "S21") (pinfunction "SPI_MISO_S21") (pintype "bidirectional"))
    )
    (net (code "56") (name "SPK_LN") (class "Default")
      (node (ref "C31") (pin "1") (pinfunction "1_1") (pintype "passive"))
      (node (ref "FB10") (pin "2") (pinfunction "P$2_2") (pintype "passive"))
      (node (ref "X1") (pin "1") (pinfunction "1_1") (pintype "passive"))
    )
    (net (code "57") (name "SPK_LP") (class "Default")
      (node (ref "C30") (pin "1") (pinfunction "1_1") (pintype "passive"))
      (node (ref "FB9") (pin "2") (pinfunction "P$2_2") (pintype "passive"))
      (node (ref "X1") (pin "2") (pinfunction "2_2") (pintype "passive"))
    )
    (net (code "58") (name "SPK_RN") (class "Default")
      (node (ref "C28") (pin "1") (pinfunction "1_1") (pintype "passive"))
      (node (ref "FB7") (pin "2") (pinfunction "P$2_2") (pintype "passive"))
      (node (ref "X5") (pin "1") (pinfunction "1_1") (pintype "passive"))
    )
    (net (code "59") (name "SPK_RP") (class "Default")
      (node (ref "C29") (pin "1") (pinfunction "1_1") (pintype "passive"))
      (node (ref "FB8") (pin "2") (pinfunction "P$2_2") (pintype "passive"))
      (node (ref "X5") (pin "2") (pinfunction "2_2") (pintype "passive"))
    )
    (net (code "60") (name "TFT_CS") (class "Default")
      (node (ref "CONN1") (pin "16") (pinfunction "16_16") (pintype "passive"))
      (node (ref "RPI1") (pin "24") (pinfunction "#SPI_CE0_24") (pintype "bidirectional"))
      (node (ref "RPI1") (pin "S24") (pinfunction "#SPI_CE0_S24") (pintype "bidirectional"))
      (node (ref "TFT2") (pin "18") (pinfunction "~{CS}_18") (pintype "input"))
    )
    (net (code "61") (name "TFT_DC") (class "Default")
      (node (ref "CONN1") (pin "12") (pinfunction "12_12") (pintype "passive"))
      (node (ref "RPI1") (pin "22") (pinfunction "GPIO25_22") (pintype "bidirectional"))
      (node (ref "RPI1") (pin "S22") (pinfunction "GPIO25_S22") (pintype "bidirectional"))
      (node (ref "TFT2") (pin "16") (pinfunction "~{WR}/D~{C}_16") (pintype "input"))
    )
    (net (code "62") (name "TFT_MOSI") (class "Default")
      (node (ref "CONN1") (pin "13") (pinfunction "13_13") (pintype "passive"))
      (node (ref "RPI1") (pin "19") (pinfunction "SPI_MOSI_19") (pintype "bidirectional"))
      (node (ref "RPI1") (pin "S19") (pinfunction "SPI_MOSI_S19") (pintype "bidirectional"))
      (node (ref "TFT2") (pin "21") (pinfunction "SDA_21") (pintype "bidirectional"))
    )
    (net (code "63") (name "TFT_RESET") (class "Default")
      (node (ref "IC4") (pin "2") (pinfunction "/RESET_2") (pintype "output"))
      (node (ref "R1") (pin "1") (pinfunction "1_1") (pintype "passive"))
      (node (ref "TFT2") (pin "20") (pinfunction "RESET_20") (pintype "input"))
    )
    (net (code "64") (name "TFT_SCLK") (class "Default")
      (node (ref "CONN1") (pin "15") (pinfunction "15_15") (pintype "passive"))
      (node (ref "RPI1") (pin "23") (pinfunction "SPI_SCLK_23") (pintype "bidirectional"))
      (node (ref "RPI1") (pin "S23") (pinfunction "SPI_SCLK_S23") (pintype "bidirectional"))
      (node (ref "TFT2") (pin "17") (pinfunction "RS/CLK_17") (pintype "input"))
    )
    (net (code "65") (name "TXD") (class "Default")
      (node (ref "CONN1") (pin "3") (pinfunction "3_3") (pintype "passive"))
      (node (ref "RPI1") (pin "8") (pinfunction "TXD_8") (pintype "bidirectional"))
      (node (ref "RPI1") (pin "S8") (pinfunction "TXD_S8") (pintype "bidirectional"))
    )
    (net (code "66") (name "VCC") (class "Default")
      (node (ref "C34") (pin "1") (pinfunction "1_1") (pintype "passive"))
      (node (ref "NEOPIX") (pin "2") (pinfunction "2_2") (pintype "passive"))
      (node (ref "SENSE") (pin "2") (pinfunction "2_2") (pintype "passive"))
      (node (ref "SJ1") (pin "2") (pinfunction "2_2") (pintype "passive"))
    )
    (net (code "67") (name "VMID") (class "Default")
      (node (ref "C1") (pin "1") (pinfunction "1_1") (pintype "passive"))
      (node (ref "C7") (pin "1") (pinfunction "1_1") (pintype "passive"))
      (node (ref "IC3") (pin "27") (pinfunction "VMID_27") (pintype "input"))
    )
    (net (code "68") (name "unconnected-(IC3-LINPUT2-Pad3)") (class "Default")
      (node (ref "IC3") (pin "3") (pinfunction "LINPUT2_3") (pintype "input"))
    )
    (net (code "69") (name "unconnected-(IC3-LINPUT3-Pad2)") (class "Default")
      (node (ref "IC3") (pin "2") (pinfunction "LINPUT3_2") (pintype "input"))
    )
    (net (code "70") (name "unconnected-(IC3-OUT3-Pad30)") (class "Default")
      (node (ref "IC3") (pin "30") (pinfunction "OUT3_30") (pintype "output"))
    )
    (net (code "71") (name "unconnected-(IC3-RINPUT2-Pad6)") (class "Default")
      (node (ref "IC3") (pin "6") (pinfunction "RINPUT2_6") (pintype "input"))
    )
    (net (code "72") (name "unconnected-(IC3-RINPUT3-Pad7)") (class "Default")
      (node (ref "IC3") (pin "7") (pinfunction "RINPUT3_7") (pintype "input"))
    )
    (net (code "73") (name "unconnected-(LED3-CKO-Pad5)") (class "Default")
      (node (ref "LED3") (pin "5") (pinfunction "CKO_5") (pintype "output"))
    )
    (net (code "74") (name "unconnected-(LED3-DO-Pad6)") (class "Default")
      (node (ref "LED3") (pin "6") (pinfunction "DO_6") (pintype "output"))
    )
    (net (code "75") (name "unconnected-(TFT2-TE-Pad19)") (class "Default")
      (node (ref "TFT2") (pin "19") (pinfunction "TE_19") (pintype "output"))
    )
    (net (code "76") (name "unconnected-(U3-P4-Pad4)") (class "Default")
      (node (ref "U3") (pin "4") (pinfunction "P4_4") (pintype "bidirectional"))
    )
  )
)
